# Tasmota_ESP32C6-6c.net
KiCad netlist of a schematic drawn in EAGLE
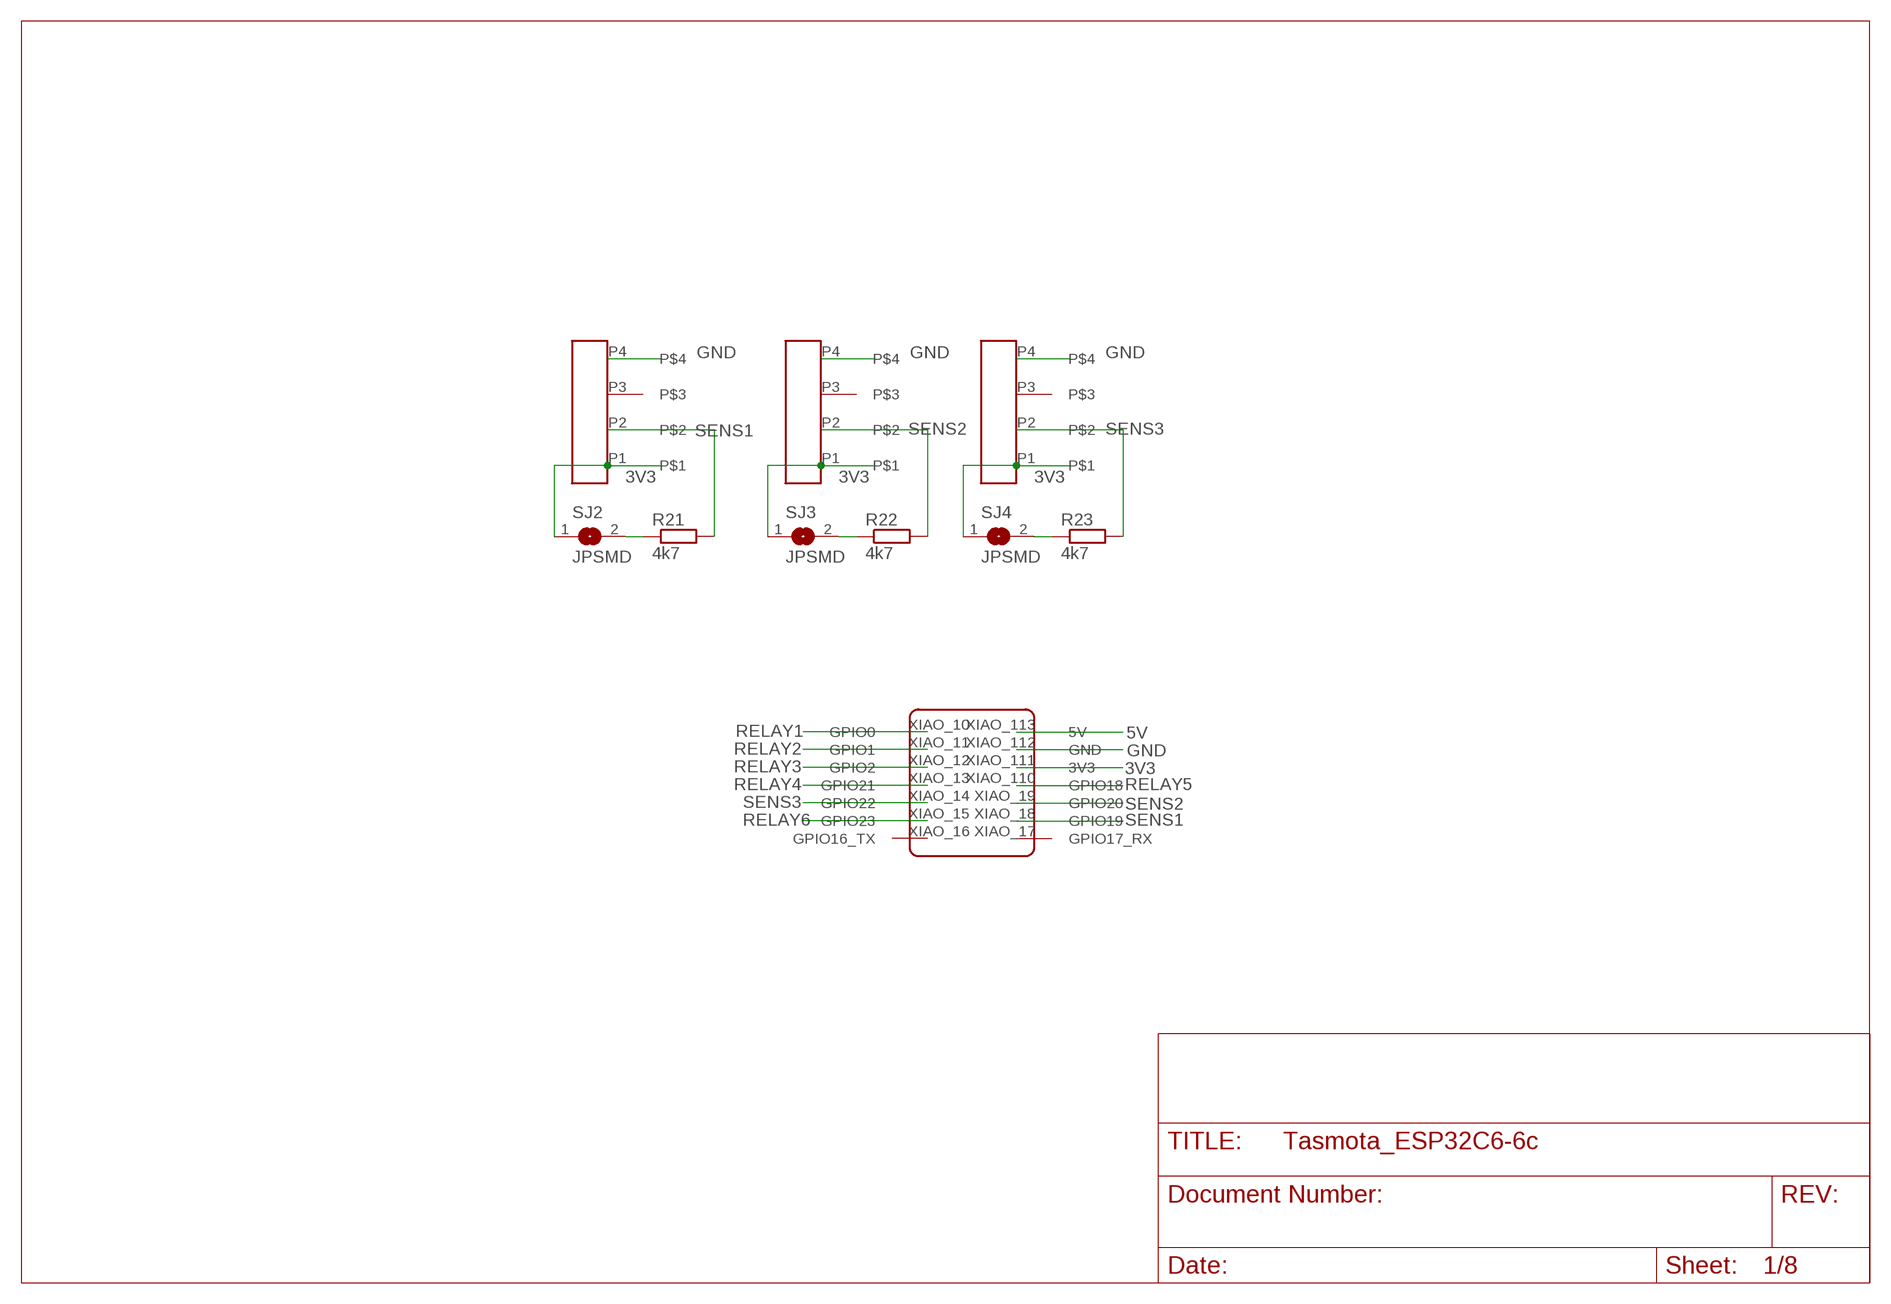
[diagram p0: schematic, sheet 1]
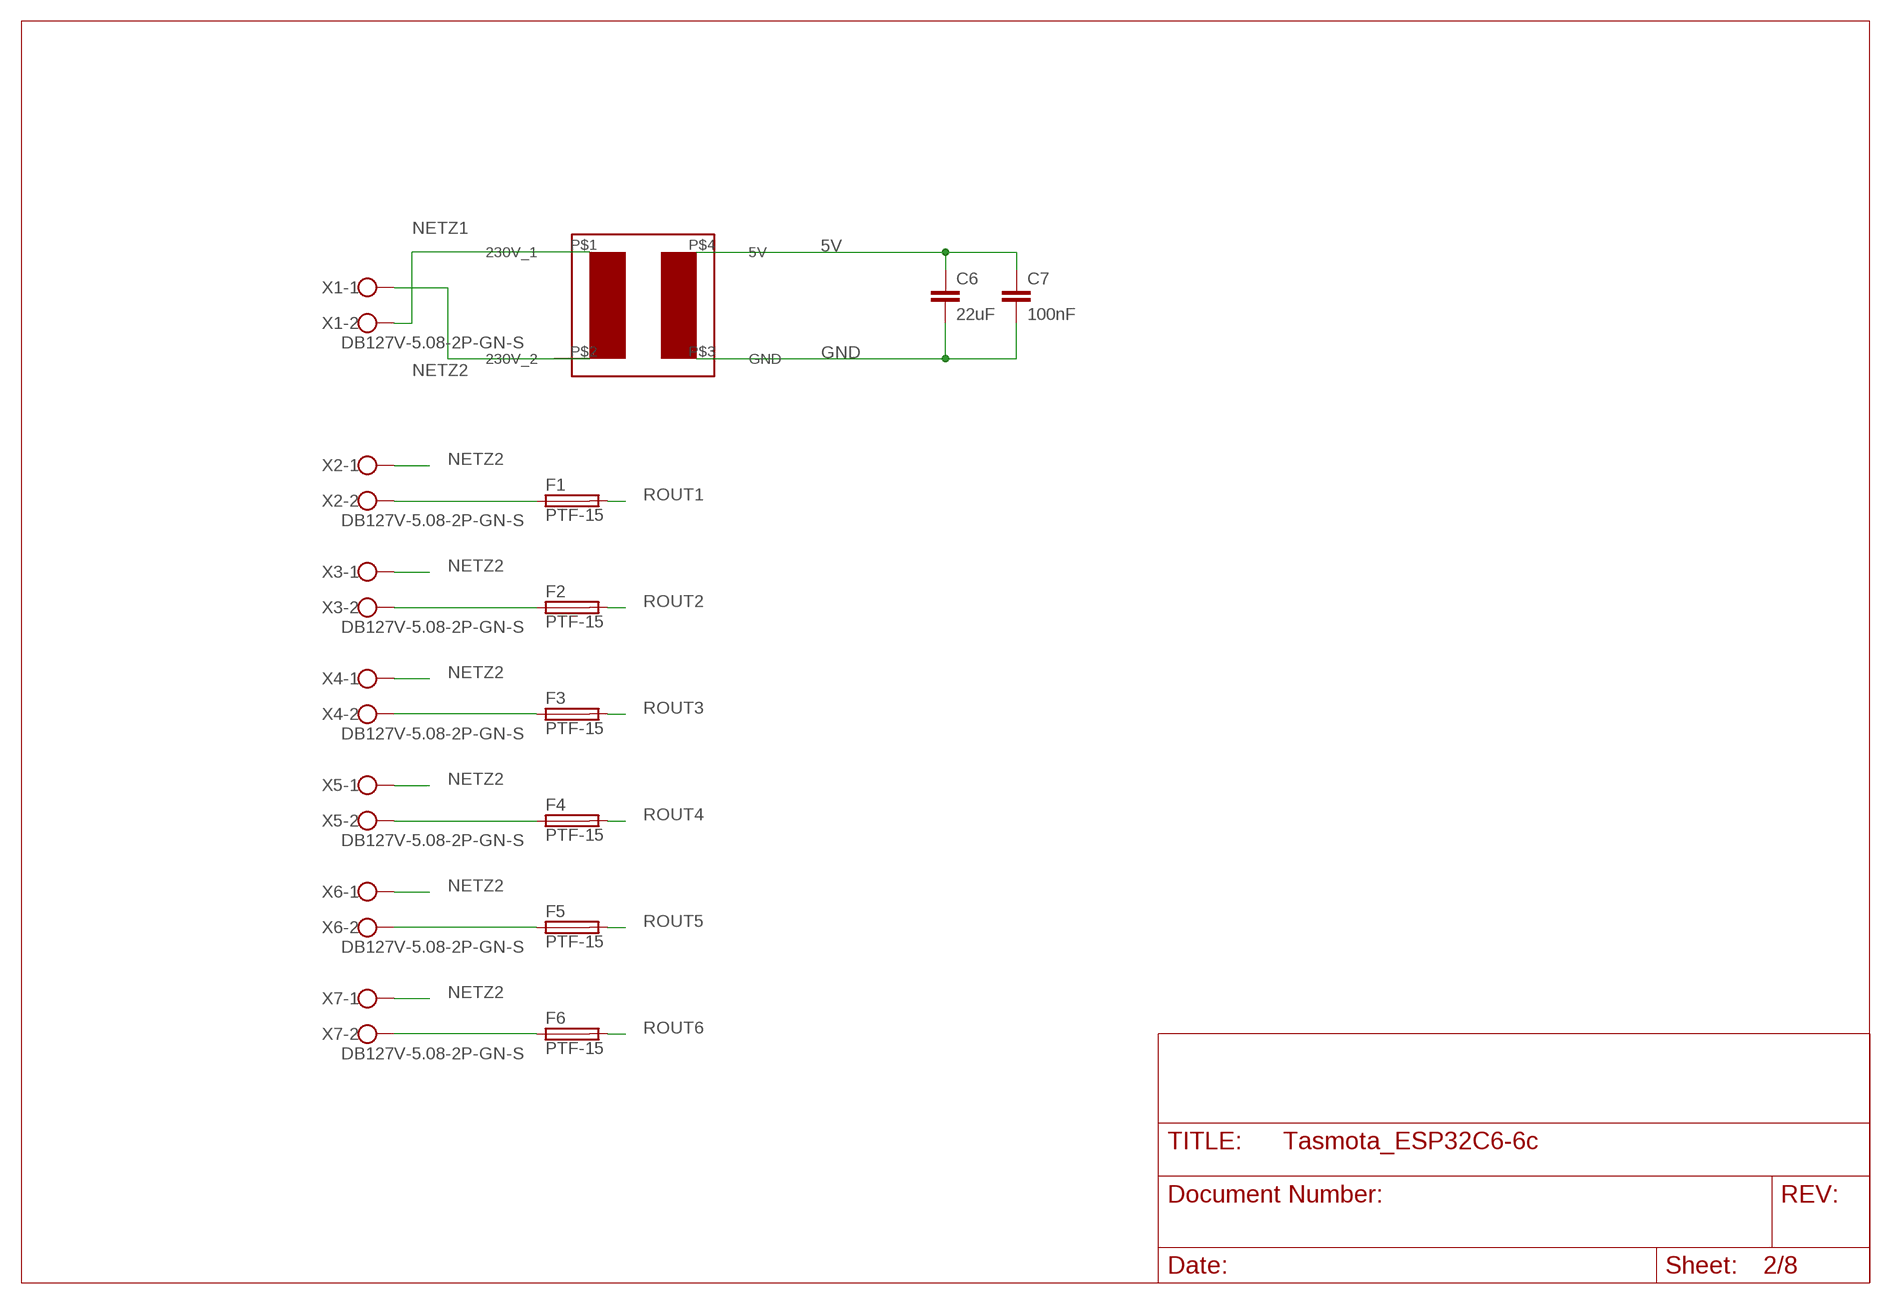
[diagram p1: schematic, sheet 2]
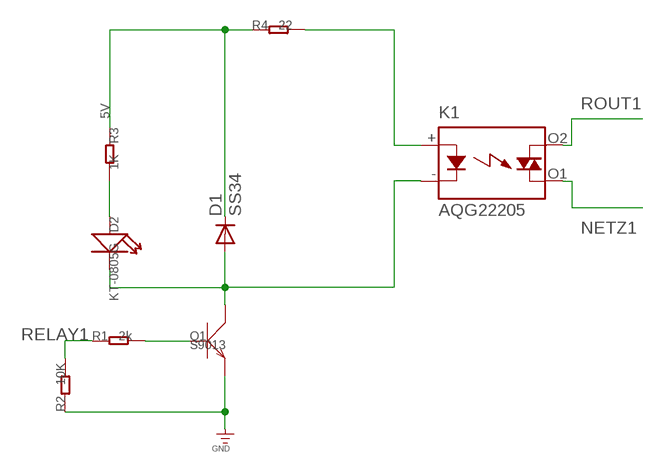
[diagram p2: schematic, sheet 3]
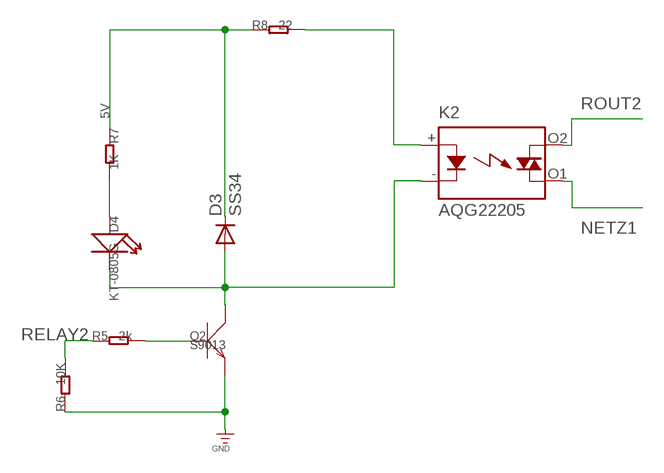
[diagram p3: schematic, sheet 4]
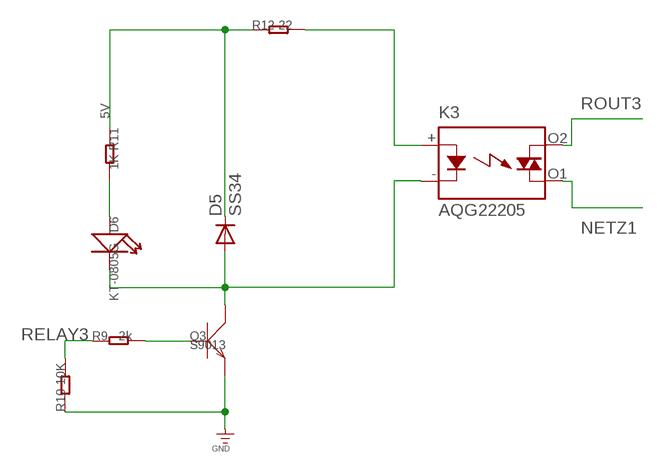
[diagram p4: schematic, sheet 5]
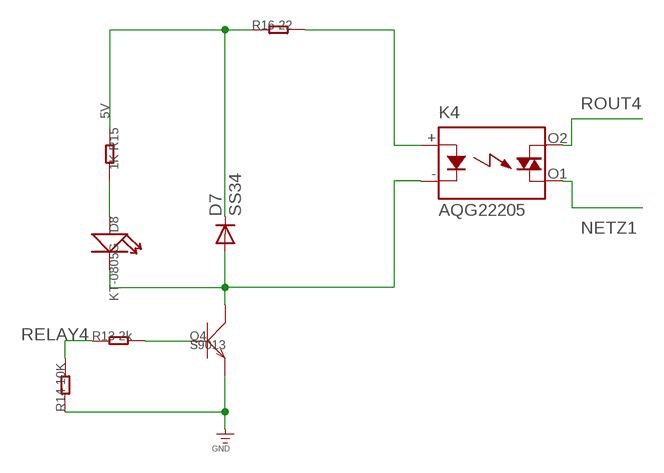
[diagram p5: schematic, sheet 6]
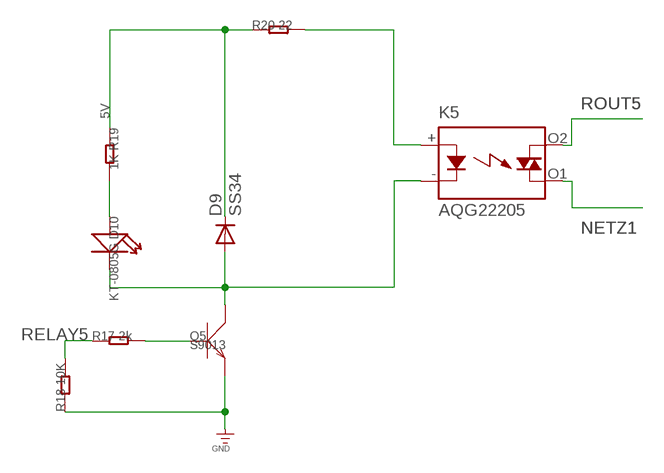
[diagram p6: schematic, sheet 7]
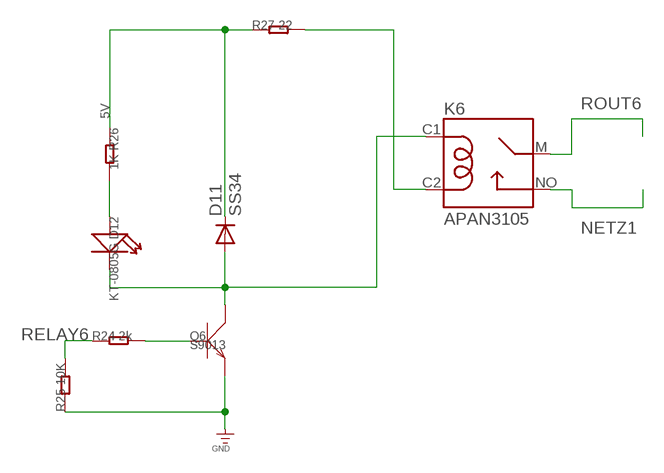
[diagram p7: schematic, sheet 8]

(export (version "E")
  (design (tool "Eeschema 10.0.6"))
  (components
    (comp (ref "R21")
      (value "4k7")
      (footprint "eagle-import:R0805")
      (libsource (lib "eagle-import") (part "R-EU_R0805"))
    )
    (comp (ref "R22")
      (value "4k7")
      (footprint "eagle-import:R0805")
      (libsource (lib "eagle-import") (part "R-EU_R0805"))
    )
    (comp (ref "R23")
      (value "4k7")
      (footprint "eagle-import:R0805")
      (libsource (lib "eagle-import") (part "R-EU_R0805"))
    )
    (comp (ref "SENSOR1")
      (value "GMX-N-44")
      (footprint "eagle-import:GMX-N-4")
      (libsource (lib "eagle-import") (part "GMX-N-4"))
    )
    (comp (ref "SENSOR2")
      (value "GMX-N-44")
      (footprint "eagle-import:GMX-N-4")
      (libsource (lib "eagle-import") (part "GMX-N-4"))
    )
    (comp (ref "SENSOR3")
      (value "GMX-N-44")
      (footprint "eagle-import:GMX-N-4")
      (libsource (lib "eagle-import") (part "GMX-N-4"))
    )
    (comp (ref "SJ2")
      (value "JPSMD")
      (footprint "eagle-import:SJ")
      (libsource (lib "eagle-import") (part "SJ"))
    )
    (comp (ref "SJ3")
      (value "JPSMD")
      (footprint "eagle-import:SJ")
      (libsource (lib "eagle-import") (part "SJ"))
    )
    (comp (ref "SJ4")
      (value "JPSMD")
      (footprint "eagle-import:SJ")
      (libsource (lib "eagle-import") (part "SJ"))
    )
    (comp (ref "U$1")
      (value "1x7P")
      (footprint "eagle-import:XIAO_ESP32C6")
      (libsource (lib "eagle-import") (part "XIAO_ESP32C6"))
    )
    (comp (ref "D1")
      (value "SS34")
      (footprint "eagle-import:DO-214AC")
      (libsource (lib "eagle-import") (part "DIODE-DO-214AC"))
    )
    (comp (ref "D2")
      (value "KT-0805G")
      (footprint "eagle-import:LED-0805")
      (libsource (lib "eagle-import") (part "LED'0805'"))
    )
    (comp (ref "K1")
      (value "AQG22205")
      (footprint "eagle-import:AQG")
      (libsource (lib "eagle-import") (part "AQG22205"))
    )
    (comp (ref "Q1")
      (value "S9013")
      (footprint "eagle-import:SOT23")
      (libsource (lib "eagle-import") (part "TRANSISTOR-NPN-SOT23"))
    )
    (comp (ref "R1")
      (value "2k")
      (footprint "eagle-import:R0805")
      (libsource (lib "eagle-import") (part "R-0805"))
    )
    (comp (ref "R2")
      (value "10K")
      (footprint "eagle-import:R0805")
      (libsource (lib "eagle-import") (part "R-0805"))
    )
    (comp (ref "R3")
      (value "1K")
      (footprint "eagle-import:R0805")
      (libsource (lib "eagle-import") (part "R-0805"))
    )
    (comp (ref "R4")
      (value "22")
      (footprint "eagle-import:R0805")
      (libsource (lib "eagle-import") (part "R-0805"))
    )
    (comp (ref "D5")
      (value "SS34")
      (footprint "eagle-import:DO-214AC")
      (libsource (lib "eagle-import") (part "DIODE-DO-214AC"))
    )
    (comp (ref "D6")
      (value "KT-0805G")
      (footprint "eagle-import:LED-0805")
      (libsource (lib "eagle-import") (part "LED'0805'"))
    )
    (comp (ref "K3")
      (value "AQG22205")
      (footprint "eagle-import:AQG")
      (libsource (lib "eagle-import") (part "AQG22205"))
    )
    (comp (ref "Q3")
      (value "S9013")
      (footprint "eagle-import:SOT23")
      (libsource (lib "eagle-import") (part "TRANSISTOR-NPN-SOT23"))
    )
    (comp (ref "R9")
      (value "2k")
      (footprint "eagle-import:R0805")
      (libsource (lib "eagle-import") (part "R-0805"))
    )
    (comp (ref "R10")
      (value "10K")
      (footprint "eagle-import:R0805")
      (libsource (lib "eagle-import") (part "R-0805"))
    )
    (comp (ref "R11")
      (value "1K")
      (footprint "eagle-import:R0805")
      (libsource (lib "eagle-import") (part "R-0805"))
    )
    (comp (ref "R12")
      (value "22")
      (footprint "eagle-import:R0805")
      (libsource (lib "eagle-import") (part "R-0805"))
    )
    (comp (ref "D3")
      (value "SS34")
      (footprint "eagle-import:DO-214AC")
      (libsource (lib "eagle-import") (part "DIODE-DO-214AC"))
    )
    (comp (ref "D4")
      (value "KT-0805G")
      (footprint "eagle-import:LED-0805")
      (libsource (lib "eagle-import") (part "LED'0805'"))
    )
    (comp (ref "K2")
      (value "AQG22205")
      (footprint "eagle-import:AQG")
      (libsource (lib "eagle-import") (part "AQG22205"))
    )
    (comp (ref "Q2")
      (value "S9013")
      (footprint "eagle-import:SOT23")
      (libsource (lib "eagle-import") (part "TRANSISTOR-NPN-SOT23"))
    )
    (comp (ref "R5")
      (value "2k")
      (footprint "eagle-import:R0805")
      (libsource (lib "eagle-import") (part "R-0805"))
    )
    (comp (ref "R6")
      (value "10K")
      (footprint "eagle-import:R0805")
      (libsource (lib "eagle-import") (part "R-0805"))
    )
    (comp (ref "R7")
      (value "1K")
      (footprint "eagle-import:R0805")
      (libsource (lib "eagle-import") (part "R-0805"))
    )
    (comp (ref "R8")
      (value "22")
      (footprint "eagle-import:R0805")
      (libsource (lib "eagle-import") (part "R-0805"))
    )
    (comp (ref "C6")
      (value "22uF")
      (footprint "eagle-import:C0805")
      (libsource (lib "eagle-import") (part "C-EUC0805"))
    )
    (comp (ref "C7")
      (value "100nF")
      (footprint "eagle-import:C0805")
      (libsource (lib "eagle-import") (part "C-EUC0805"))
    )
    (comp (ref "F1")
      (value "PTF-15")
      (footprint "eagle-import:SH22,5")
      (fields (field (name "MF") "SCHURTER") (field (name "MPN") "0031.8201"))
      (libsource (lib "eagle-import") (part "SH22,5"))
    )
    (comp (ref "F2")
      (value "PTF-15")
      (footprint "eagle-import:SH22,5")
      (fields (field (name "MF") "SCHURTER") (field (name "MPN") "0031.8201"))
      (libsource (lib "eagle-import") (part "SH22,5"))
    )
    (comp (ref "F3")
      (value "PTF-15")
      (footprint "eagle-import:SH22,5")
      (fields (field (name "MF") "SCHURTER") (field (name "MPN") "0031.8201"))
      (libsource (lib "eagle-import") (part "SH22,5"))
    )
    (comp (ref "F4")
      (value "PTF-15")
      (footprint "eagle-import:SH22,5")
      (fields (field (name "MF") "SCHURTER") (field (name "MPN") "0031.8201"))
      (libsource (lib "eagle-import") (part "SH22,5"))
    )
    (comp (ref "F5")
      (value "PTF-15")
      (footprint "eagle-import:SH22,5")
      (fields (field (name "MF") "SCHURTER") (field (name "MPN") "0031.8201"))
      (libsource (lib "eagle-import") (part "SH22,5"))
    )
    (comp (ref "F6")
      (value "PTF-15")
      (footprint "eagle-import:SH22,5")
      (fields (field (name "MF") "SCHURTER") (field (name "MPN") "0031.8201"))
      (libsource (lib "eagle-import") (part "SH22,5"))
    )
    (comp (ref "U$3")
      (value "HAW3-220S05T2")
      (footprint "eagle-import:HAW3-220S05T2")
      (libsource (lib "eagle-import") (part "HAW3-220S05T2"))
    )
    (comp (ref "X1")
      (value "DB127V-5.08-2P-GN-S")
      (footprint "eagle-import:W237-102")
      (fields (field (name "MPN") "237-102"))
      (libsource (lib "eagle-import") (part "con-wago-500_195_W237-102"))
    )
    (comp (ref "X2")
      (value "DB127V-5.08-2P-GN-S")
      (footprint "eagle-import:W237-102")
      (fields (field (name "MPN") "237-102"))
      (libsource (lib "eagle-import") (part "W237-102"))
    )
    (comp (ref "X3")
      (value "DB127V-5.08-2P-GN-S")
      (footprint "eagle-import:W237-102")
      (fields (field (name "MPN") "237-102"))
      (libsource (lib "eagle-import") (part "W237-102"))
    )
    (comp (ref "X4")
      (value "DB127V-5.08-2P-GN-S")
      (footprint "eagle-import:W237-102")
      (fields (field (name "MPN") "237-102"))
      (libsource (lib "eagle-import") (part "W237-102"))
    )
    (comp (ref "X5")
      (value "DB127V-5.08-2P-GN-S")
      (footprint "eagle-import:W237-102")
      (fields (field (name "MPN") "237-102"))
      (libsource (lib "eagle-import") (part "W237-102"))
    )
    (comp (ref "X6")
      (value "DB127V-5.08-2P-GN-S")
      (footprint "eagle-import:W237-102")
      (fields (field (name "MPN") "237-102"))
      (libsource (lib "eagle-import") (part "W237-102"))
    )
    (comp (ref "X7")
      (value "DB127V-5.08-2P-GN-S")
      (footprint "eagle-import:W237-102")
      (fields (field (name "MPN") "237-102"))
      (libsource (lib "eagle-import") (part "W237-102"))
    )
    (comp (ref "D7")
      (value "SS34")
      (footprint "eagle-import:DO-214AC")
      (libsource (lib "eagle-import") (part "DIODE-DO-214AC"))
    )
    (comp (ref "D8")
      (value "KT-0805G")
      (footprint "eagle-import:LED-0805")
      (libsource (lib "eagle-import") (part "LED'0805'"))
    )
    (comp (ref "K4")
      (value "AQG22205")
      (footprint "eagle-import:AQG")
      (libsource (lib "eagle-import") (part "AQG22205"))
    )
    (comp (ref "Q4")
      (value "S9013")
      (footprint "eagle-import:SOT23")
      (libsource (lib "eagle-import") (part "TRANSISTOR-NPN-SOT23"))
    )
    (comp (ref "R13")
      (value "2k")
      (footprint "eagle-import:R0805")
      (libsource (lib "eagle-import") (part "R-0805"))
    )
    (comp (ref "R14")
      (value "10K")
      (footprint "eagle-import:R0805")
      (libsource (lib "eagle-import") (part "R-0805"))
    )
    (comp (ref "R15")
      (value "1K")
      (footprint "eagle-import:R0805")
      (libsource (lib "eagle-import") (part "R-0805"))
    )
    (comp (ref "R16")
      (value "22")
      (footprint "eagle-import:R0805")
      (libsource (lib "eagle-import") (part "R-0805"))
    )
    (comp (ref "D9")
      (value "SS34")
      (footprint "eagle-import:DO-214AC")
      (libsource (lib "eagle-import") (part "DIODE-DO-214AC"))
    )
    (comp (ref "D10")
      (value "KT-0805G")
      (footprint "eagle-import:LED-0805")
      (libsource (lib "eagle-import") (part "LED'0805'"))
    )
    (comp (ref "K5")
      (value "AQG22205")
      (footprint "eagle-import:AQG")
      (libsource (lib "eagle-import") (part "AQG22205"))
    )
    (comp (ref "Q5")
      (value "S9013")
      (footprint "eagle-import:SOT23")
      (libsource (lib "eagle-import") (part "TRANSISTOR-NPN-SOT23"))
    )
    (comp (ref "R17")
      (value "2k")
      (footprint "eagle-import:R0805")
      (libsource (lib "eagle-import") (part "R-0805"))
    )
    (comp (ref "R18")
      (value "10K")
      (footprint "eagle-import:R0805")
      (libsource (lib "eagle-import") (part "R-0805"))
    )
    (comp (ref "R19")
      (value "1K")
      (footprint "eagle-import:R0805")
      (libsource (lib "eagle-import") (part "R-0805"))
    )
    (comp (ref "R20")
      (value "22")
      (footprint "eagle-import:R0805")
      (libsource (lib "eagle-import") (part "R-0805"))
    )
    (comp (ref "D11")
      (value "SS34")
      (footprint "eagle-import:DO-214AC")
      (libsource (lib "eagle-import") (part "DIODE-DO-214AC"))
    )
    (comp (ref "D12")
      (value "KT-0805G")
      (footprint "eagle-import:LED-0805")
      (libsource (lib "eagle-import") (part "LED'0805'"))
    )
    (comp (ref "K6")
      (value "APAN3105")
      (footprint "eagle-import:RELAY_APAN3105")
      (fields (field (name "MF") "Panasonic"))
      (libsource (lib "eagle-import") (part "APAN3105"))
    )
    (comp (ref "Q6")
      (value "S9013")
      (footprint "eagle-import:SOT23")
      (libsource (lib "eagle-import") (part "TRANSISTOR-NPN-SOT23"))
    )
    (comp (ref "R24")
      (value "2k")
      (footprint "eagle-import:R0805")
      (libsource (lib "eagle-import") (part "R-0805"))
    )
    (comp (ref "R25")
      (value "10K")
      (footprint "eagle-import:R0805")
      (libsource (lib "eagle-import") (part "R-0805"))
    )
    (comp (ref "R26")
      (value "1K")
      (footprint "eagle-import:R0805")
      (libsource (lib "eagle-import") (part "R-0805"))
    )
    (comp (ref "R27")
      (value "22")
      (footprint "eagle-import:R0805")
      (libsource (lib "eagle-import") (part "R-0805"))
    )
  )
  (nets
    (net (code "1") (name "3V3") (class "Default")
      (node (ref "SENSOR1") (pin "P1") (pinfunction "P$1_P1") (pintype "bidirectional"))
      (node (ref "SENSOR2") (pin "P1") (pinfunction "P$1_P1") (pintype "bidirectional"))
      (node (ref "SENSOR3") (pin "P1") (pinfunction "P$1_P1") (pintype "bidirectional"))
      (node (ref "SJ2") (pin "1") (pinfunction "1_1") (pintype "passive"))
      (node (ref "SJ3") (pin "1") (pinfunction "1_1") (pintype "passive"))
      (node (ref "SJ4") (pin "1") (pinfunction "1_1") (pintype "passive"))
      (node (ref "U$1") (pin "XIAO_111") (pinfunction "3V3_XIAO_111") (pintype "power_in"))
    )
    (net (code "2") (name "5V") (class "Default")
      (node (ref "C6") (pin "1") (pinfunction "1_1") (pintype "passive"))
      (node (ref "C7") (pin "1") (pinfunction "1_1") (pintype "passive"))
      (node (ref "D1") (pin "C") (pinfunction "C_C") (pintype "passive"))
      (node (ref "D11") (pin "C") (pinfunction "C_C") (pintype "passive"))
      (node (ref "D3") (pin "C") (pinfunction "C_C") (pintype "passive"))
      (node (ref "D5") (pin "C") (pinfunction "C_C") (pintype "passive"))
      (node (ref "D7") (pin "C") (pinfunction "C_C") (pintype "passive"))
      (node (ref "D9") (pin "C") (pinfunction "C_C") (pintype "passive"))
      (node (ref "R11") (pin "1") (pinfunction "1_1") (pintype "passive"))
      (node (ref "R12") (pin "1") (pinfunction "1_1") (pintype "passive"))
      (node (ref "R15") (pin "1") (pinfunction "1_1") (pintype "passive"))
      (node (ref "R16") (pin "1") (pinfunction "1_1") (pintype "passive"))
      (node (ref "R19") (pin "1") (pinfunction "1_1") (pintype "passive"))
      (node (ref "R20") (pin "1") (pinfunction "1_1") (pintype "passive"))
      (node (ref "R26") (pin "1") (pinfunction "1_1") (pintype "passive"))
      (node (ref "R27") (pin "1") (pinfunction "1_1") (pintype "passive"))
      (node (ref "R3") (pin "1") (pinfunction "1_1") (pintype "passive"))
      (node (ref "R4") (pin "1") (pinfunction "1_1") (pintype "passive"))
      (node (ref "R7") (pin "1") (pinfunction "1_1") (pintype "passive"))
      (node (ref "R8") (pin "1") (pinfunction "1_1") (pintype "passive"))
      (node (ref "U$1") (pin "XIAO_113") (pinfunction "5V_XIAO_113") (pintype "power_in"))
      (node (ref "U$3") (pin "P$4") (pinfunction "5V_P$4") (pintype "bidirectional"))
    )
    (net (code "3") (name "GND") (class "Default")
      (node (ref "C6") (pin "2") (pinfunction "2_2") (pintype "passive"))
      (node (ref "C7") (pin "2") (pinfunction "2_2") (pintype "passive"))
      (node (ref "Q1") (pin "2") (pinfunction "E_2") (pintype "passive"))
      (node (ref "Q2") (pin "2") (pinfunction "E_2") (pintype "passive"))
      (node (ref "Q3") (pin "2") (pinfunction "E_2") (pintype "passive"))
      (node (ref "Q4") (pin "2") (pinfunction "E_2") (pintype "passive"))
      (node (ref "Q5") (pin "2") (pinfunction "E_2") (pintype "passive"))
      (node (ref "Q6") (pin "2") (pinfunction "E_2") (pintype "passive"))
      (node (ref "R10") (pin "1") (pinfunction "1_1") (pintype "passive"))
      (node (ref "R14") (pin "1") (pinfunction "1_1") (pintype "passive"))
      (node (ref "R18") (pin "1") (pinfunction "1_1") (pintype "passive"))
      (node (ref "R2") (pin "1") (pinfunction "1_1") (pintype "passive"))
      (node (ref "R25") (pin "1") (pinfunction "1_1") (pintype "passive"))
      (node (ref "R6") (pin "1") (pinfunction "1_1") (pintype "passive"))
      (node (ref "SENSOR1") (pin "P4") (pinfunction "P$4_P4") (pintype "bidirectional"))
      (node (ref "SENSOR2") (pin "P4") (pinfunction "P$4_P4") (pintype "bidirectional"))
      (node (ref "SENSOR3") (pin "P4") (pinfunction "P$4_P4") (pintype "bidirectional"))
      (node (ref "U$1") (pin "XIAO_112") (pinfunction "GND_XIAO_112") (pintype "power_in"))
      (node (ref "U$3") (pin "P$3") (pinfunction "GND_P$3") (pintype "bidirectional"))
    )
    (net (code "4") (name "NETZ1") (class "Default")
      (node (ref "K1") (pin "O1") (pinfunction "DS2_O1") (pintype "passive"))
      (node (ref "K2") (pin "O1") (pinfunction "DS2_O1") (pintype "passive"))
      (node (ref "K3") (pin "O1") (pinfunction "DS2_O1") (pintype "passive"))
      (node (ref "K4") (pin "O1") (pinfunction "DS2_O1") (pintype "passive"))
      (node (ref "K5") (pin "O1") (pinfunction "DS2_O1") (pintype "passive"))
      (node (ref "K6") (pin "NO") (pinfunction "NO_NO") (pintype "passive"))
      (node (ref "U$3") (pin "P$1") (pinfunction "230V_1_P$1") (pintype "bidirectional"))
      (node (ref "X1") (pin "2") (pinfunction "KL_2") (pintype "passive"))
    )
    (net (code "5") (name "NETZ2") (class "Default")
      (node (ref "U$3") (pin "P$2") (pinfunction "230V_2_P$2") (pintype "bidirectional"))
      (node (ref "X1") (pin "1") (pinfunction "KL_1") (pintype "passive"))
      (node (ref "X2") (pin "1") (pinfunction "KL_1") (pintype "passive"))
      (node (ref "X3") (pin "1") (pinfunction "KL_1") (pintype "passive"))
      (node (ref "X4") (pin "1") (pinfunction "KL_1") (pintype "passive"))
      (node (ref "X5") (pin "1") (pinfunction "KL_1") (pintype "passive"))
      (node (ref "X6") (pin "1") (pinfunction "KL_1") (pintype "passive"))
      (node (ref "X7") (pin "1") (pinfunction "KL_1") (pintype "passive"))
    )
    (net (code "6") (name "Net-(D2-Pad+)") (class "Default")
      (node (ref "D2") (pin "+") (pinfunction "+_+") (pintype "passive"))
      (node (ref "R3") (pin "2") (pinfunction "2_2") (pintype "passive"))
    )
    (net (code "7") (name "Net-(D4-Pad+)") (class "Default")
      (node (ref "D4") (pin "+") (pinfunction "+_+") (pintype "passive"))
      (node (ref "R7") (pin "2") (pinfunction "2_2") (pintype "passive"))
    )
    (net (code "8") (name "Net-(D6-Pad+)") (class "Default")
      (node (ref "D6") (pin "+") (pinfunction "+_+") (pintype "passive"))
      (node (ref "R11") (pin "2") (pinfunction "2_2") (pintype "passive"))
    )
    (net (code "9") (name "Net-(D8-Pad+)") (class "Default")
      (node (ref "D8") (pin "+") (pinfunction "+_+") (pintype "passive"))
      (node (ref "R15") (pin "2") (pinfunction "2_2") (pintype "passive"))
    )
    (net (code "10") (name "Net-(D10-Pad+)") (class "Default")
      (node (ref "D10") (pin "+") (pinfunction "+_+") (pintype "passive"))
      (node (ref "R19") (pin "2") (pinfunction "2_2") (pintype "passive"))
    )
    (net (code "11") (name "Net-(D12-Pad+)") (class "Default")
      (node (ref "D12") (pin "+") (pinfunction "+_+") (pintype "passive"))
      (node (ref "R26") (pin "2") (pinfunction "2_2") (pintype "passive"))
    )
    (net (code "12") (name "Net-(K1-A)") (class "Default")
      (node (ref "K1") (pin "+") (pinfunction "A_+") (pintype "passive"))
      (node (ref "R4") (pin "2") (pinfunction "2_2") (pintype "passive"))
    )
    (net (code "13") (name "Net-(K1-K)") (class "Default")
      (node (ref "D1") (pin "A") (pinfunction "A_A") (pintype "passive"))
      (node (ref "D2") (pin "-") (pinfunction "-_-") (pintype "passive"))
      (node (ref "K1") (pin "-") (pinfunction "K_-") (pintype "passive"))
      (node (ref "Q1") (pin "3") (pinfunction "C_3") (pintype "passive"))
    )
    (net (code "14") (name "Net-(K2-A)") (class "Default")
      (node (ref "K2") (pin "+") (pinfunction "A_+") (pintype "passive"))
      (node (ref "R8") (pin "2") (pinfunction "2_2") (pintype "passive"))
    )
    (net (code "15") (name "Net-(K2-K)") (class "Default")
      (node (ref "D3") (pin "A") (pinfunction "A_A") (pintype "passive"))
      (node (ref "D4") (pin "-") (pinfunction "-_-") (pintype "passive"))
      (node (ref "K2") (pin "-") (pinfunction "K_-") (pintype "passive"))
      (node (ref "Q2") (pin "3") (pinfunction "C_3") (pintype "passive"))
    )
    (net (code "16") (name "Net-(K3-A)") (class "Default")
      (node (ref "K3") (pin "+") (pinfunction "A_+") (pintype "passive"))
      (node (ref "R12") (pin "2") (pinfunction "2_2") (pintype "passive"))
    )
    (net (code "17") (name "Net-(K3-K)") (class "Default")
      (node (ref "D5") (pin "A") (pinfunction "A_A") (pintype "passive"))
      (node (ref "D6") (pin "-") (pinfunction "-_-") (pintype "passive"))
      (node (ref "K3") (pin "-") (pinfunction "K_-") (pintype "passive"))
      (node (ref "Q3") (pin "3") (pinfunction "C_3") (pintype "passive"))
    )
    (net (code "18") (name "Net-(K4-A)") (class "Default")
      (node (ref "K4") (pin "+") (pinfunction "A_+") (pintype "passive"))
      (node (ref "R16") (pin "2") (pinfunction "2_2") (pintype "passive"))
    )
    (net (code "19") (name "Net-(K4-K)") (class "Default")
      (node (ref "D7") (pin "A") (pinfunction "A_A") (pintype "passive"))
      (node (ref "D8") (pin "-") (pinfunction "-_-") (pintype "passive"))
      (node (ref "K4") (pin "-") (pinfunction "K_-") (pintype "passive"))
      (node (ref "Q4") (pin "3") (pinfunction "C_3") (pintype "passive"))
    )
    (net (code "20") (name "Net-(K5-A)") (class "Default")
      (node (ref "K5") (pin "+") (pinfunction "A_+") (pintype "passive"))
      (node (ref "R20") (pin "2") (pinfunction "2_2") (pintype "passive"))
    )
    (net (code "21") (name "Net-(K5-K)") (class "Default")
      (node (ref "D10") (pin "-") (pinfunction "-_-") (pintype "passive"))
      (node (ref "D9") (pin "A") (pinfunction "A_A") (pintype "passive"))
      (node (ref "K5") (pin "-") (pinfunction "K_-") (pintype "passive"))
      (node (ref "Q5") (pin "3") (pinfunction "C_3") (pintype "passive"))
    )
    (net (code "22") (name "Net-(K6-PadC2)") (class "Default")
      (node (ref "K6") (pin "C2") (pinfunction "C2_C2") (pintype "passive"))
      (node (ref "R27") (pin "2") (pinfunction "2_2") (pintype "passive"))
    )
    (net (code "23") (name "Net-(Q1-B)") (class "Default")
      (node (ref "Q1") (pin "1") (pinfunction "B_1") (pintype "passive"))
      (node (ref "R1") (pin "2") (pinfunction "2_2") (pintype "passive"))
    )
    (net (code "24") (name "Net-(Q2-B)") (class "Default")
      (node (ref "Q2") (pin "1") (pinfunction "B_1") (pintype "passive"))
      (node (ref "R5") (pin "2") (pinfunction "2_2") (pintype "passive"))
    )
    (net (code "25") (name "Net-(Q3-B)") (class "Default")
      (node (ref "Q3") (pin "1") (pinfunction "B_1") (pintype "passive"))
      (node (ref "R9") (pin "2") (pinfunction "2_2") (pintype "passive"))
    )
    (net (code "26") (name "Net-(Q4-B)") (class "Default")
      (node (ref "Q4") (pin "1") (pinfunction "B_1") (pintype "passive"))
      (node (ref "R13") (pin "2") (pinfunction "2_2") (pintype "passive"))
    )
    (net (code "27") (name "Net-(Q5-B)") (class "Default")
      (node (ref "Q5") (pin "1") (pinfunction "B_1") (pintype "passive"))
      (node (ref "R17") (pin "2") (pinfunction "2_2") (pintype "passive"))
    )
    (net (code "28") (name "Net-(Q6-B)") (class "Default")
      (node (ref "Q6") (pin "1") (pinfunction "B_1") (pintype "passive"))
      (node (ref "R24") (pin "2") (pinfunction "2_2") (pintype "passive"))
    )
    (net (code "29") (name "Net-(Q6-C)") (class "Default")
      (node (ref "D11") (pin "A") (pinfunction "A_A") (pintype "passive"))
      (node (ref "D12") (pin "-") (pinfunction "-_-") (pintype "passive"))
      (node (ref "K6") (pin "C1") (pinfunction "C1_C1") (pintype "passive"))
      (node (ref "Q6") (pin "3") (pinfunction "C_3") (pintype "passive"))
    )
    (net (code "30") (name "Net-(R21-Pad1)") (class "Default")
      (node (ref "R21") (pin "1") (pinfunction "1_1") (pintype "passive"))
      (node (ref "SJ2") (pin "2") (pinfunction "2_2") (pintype "passive"))
    )
    (net (code "31") (name "Net-(R22-Pad1)") (class "Default")
      (node (ref "R22") (pin "1") (pinfunction "1_1") (pintype "passive"))
      (node (ref "SJ3") (pin "2") (pinfunction "2_2") (pintype "passive"))
    )
    (net (code "32") (name "Net-(R23-Pad1)") (class "Default")
      (node (ref "R23") (pin "1") (pinfunction "1_1") (pintype "passive"))
      (node (ref "SJ4") (pin "2") (pinfunction "2_2") (pintype "passive"))
    )
    (net (code "33") (name "Net-(X2B-KL)") (class "Default")
      (node (ref "F1") (pin "1") (pinfunction "1_1") (pintype "passive"))
      (node (ref "X2") (pin "2") (pinfunction "KL_2") (pintype "passive"))
    )
    (net (code "34") (name "Net-(X3B-KL)") (class "Default")
      (node (ref "F2") (pin "1") (pinfunction "1_1") (pintype "passive"))
      (node (ref "X3") (pin "2") (pinfunction "KL_2") (pintype "passive"))
    )
    (net (code "35") (name "Net-(X4B-KL)") (class "Default")
      (node (ref "F3") (pin "1") (pinfunction "1_1") (pintype "passive"))
      (node (ref "X4") (pin "2") (pinfunction "KL_2") (pintype "passive"))
    )
    (net (code "36") (name "Net-(X5B-KL)") (class "Default")
      (node (ref "F4") (pin "1") (pinfunction "1_1") (pintype "passive"))
      (node (ref "X5") (pin "2") (pinfunction "KL_2") (pintype "passive"))
    )
    (net (code "37") (name "Net-(X6B-KL)") (class "Default")
      (node (ref "F5") (pin "1") (pinfunction "1_1") (pintype "passive"))
      (node (ref "X6") (pin "2") (pinfunction "KL_2") (pintype "passive"))
    )
    (net (code "38") (name "Net-(X7B-KL)") (class "Default")
      (node (ref "F6") (pin "1") (pinfunction "1_1") (pintype "passive"))
      (node (ref "X7") (pin "2") (pinfunction "KL_2") (pintype "passive"))
    )
    (net (code "39") (name "RELAY1") (class "Default")
      (node (ref "R1") (pin "1") (pinfunction "1_1") (pintype "passive"))
      (node (ref "R2") (pin "2") (pinfunction "2_2") (pintype "passive"))
      (node (ref "U$1") (pin "XIAO_10") (pinfunction "GPIO0_XIAO_10") (pintype "bidirectional"))
    )
    (net (code "40") (name "RELAY2") (class "Default")
      (node (ref "R5") (pin "1") (pinfunction "1_1") (pintype "passive"))
      (node (ref "R6") (pin "2") (pinfunction "2_2") (pintype "passive"))
      (node (ref "U$1") (pin "XIAO_11") (pinfunction "GPIO1_XIAO_11") (pintype "bidirectional"))
    )
    (net (code "41") (name "RELAY3") (class "Default")
      (node (ref "R10") (pin "2") (pinfunction "2_2") (pintype "passive"))
      (node (ref "R9") (pin "1") (pinfunction "1_1") (pintype "passive"))
      (node (ref "U$1") (pin "XIAO_12") (pinfunction "GPIO2_XIAO_12") (pintype "bidirectional"))
    )
    (net (code "42") (name "RELAY4") (class "Default")
      (node (ref "R13") (pin "1") (pinfunction "1_1") (pintype "passive"))
      (node (ref "R14") (pin "2") (pinfunction "2_2") (pintype "passive"))
      (node (ref "U$1") (pin "XIAO_13") (pinfunction "GPIO21_XIAO_13") (pintype "bidirectional"))
    )
    (net (code "43") (name "RELAY5") (class "Default")
      (node (ref "R17") (pin "1") (pinfunction "1_1") (pintype "passive"))
      (node (ref "R18") (pin "2") (pinfunction "2_2") (pintype "passive"))
      (node (ref "U$1") (pin "XIAO_110") (pinfunction "GPIO18_XIAO_110") (pintype "bidirectional"))
    )
    (net (code "44") (name "RELAY6") (class "Default")
      (node (ref "R24") (pin "1") (pinfunction "1_1") (pintype "passive"))
      (node (ref "R25") (pin "2") (pinfunction "2_2") (pintype "passive"))
      (node (ref "U$1") (pin "XIAO_15") (pinfunction "GPIO23_XIAO_15") (pintype "bidirectional"))
    )
    (net (code "45") (name "ROUT1") (class "Default")
      (node (ref "F1") (pin "2") (pinfunction "2_2") (pintype "passive"))
      (node (ref "K1") (pin "O2") (pinfunction "DS1_O2") (pintype "passive"))
    )
    (net (code "46") (name "ROUT2") (class "Default")
      (node (ref "F2") (pin "2") (pinfunction "2_2") (pintype "passive"))
      (node (ref "K2") (pin "O2") (pinfunction "DS1_O2") (pintype "passive"))
    )
    (net (code "47") (name "ROUT3") (class "Default")
      (node (ref "F3") (pin "2") (pinfunction "2_2") (pintype "passive"))
      (node (ref "K3") (pin "O2") (pinfunction "DS1_O2") (pintype "passive"))
    )
    (net (code "48") (name "ROUT4") (class "Default")
      (node (ref "F4") (pin "2") (pinfunction "2_2") (pintype "passive"))
      (node (ref "K4") (pin "O2") (pinfunction "DS1_O2") (pintype "passive"))
    )
    (net (code "49") (name "ROUT5") (class "Default")
      (node (ref "F5") (pin "2") (pinfunction "2_2") (pintype "passive"))
      (node (ref "K5") (pin "O2") (pinfunction "DS1_O2") (pintype "passive"))
    )
    (net (code "50") (name "ROUT6") (class "Default")
      (node (ref "F6") (pin "2") (pinfunction "2_2") (pintype "passive"))
      (node (ref "K6") (pin "M") (pinfunction "M_M") (pintype "passive"))
    )
    (net (code "51") (name "SENS1") (class "Default")
      (node (ref "R21") (pin "2") (pinfunction "2_2") (pintype "passive"))
      (node (ref "SENSOR1") (pin "P2") (pinfunction "P$2_P2") (pintype "bidirectional"))
      (node (ref "U$1") (pin "XIAO_18") (pinfunction "GPIO19_XIAO_18") (pintype "bidirectional"))
    )
    (net (code "52") (name "SENS2") (class "Default")
      (node (ref "R22") (pin "2") (pinfunction "2_2") (pintype "passive"))
      (node (ref "SENSOR2") (pin "P2") (pinfunction "P$2_P2") (pintype "bidirectional"))
      (node (ref "U$1") (pin "XIAO_19") (pinfunction "GPIO20_XIAO_19") (pintype "bidirectional"))
    )
    (net (code "53") (name "SENS3") (class "Default")
      (node (ref "R23") (pin "2") (pinfunction "2_2") (pintype "passive"))
      (node (ref "SENSOR3") (pin "P2") (pinfunction "P$2_P2") (pintype "bidirectional"))
      (node (ref "U$1") (pin "XIAO_14") (pinfunction "GPIO22_XIAO_14") (pintype "bidirectional"))
    )
    (net (code "54") (name "unconnected-(SENSOR1-P$3-PadP3)") (class "Default")
      (node (ref "SENSOR1") (pin "P3") (pinfunction "P$3_P3") (pintype "bidirectional"))
    )
    (net (code "55") (name "unconnected-(SENSOR2-P$3-PadP3)") (class "Default")
      (node (ref "SENSOR2") (pin "P3") (pinfunction "P$3_P3") (pintype "bidirectional"))
    )
    (net (code "56") (name "unconnected-(SENSOR3-P$3-PadP3)") (class "Default")
      (node (ref "SENSOR3") (pin "P3") (pinfunction "P$3_P3") (pintype "bidirectional"))
    )
    (net (code "57") (name "unconnected-(U$1-GPIO16_TX-PadXIAO_16)") (class "Default")
      (node (ref "U$1") (pin "XIAO_16") (pinfunction "GPIO16_TX_XIAO_16") (pintype "bidirectional"))
    )
    (net (code "58") (name "unconnected-(U$1-GPIO17_RX-PadXIAO_17)") (class "Default")
      (node (ref "U$1") (pin "XIAO_17") (pinfunction "GPIO17_RX_XIAO_17") (pintype "bidirectional"))
    )
  )
)
